# 100_H_M_interface.net
KiCad netlist of a schematic drawn in Altium Designer
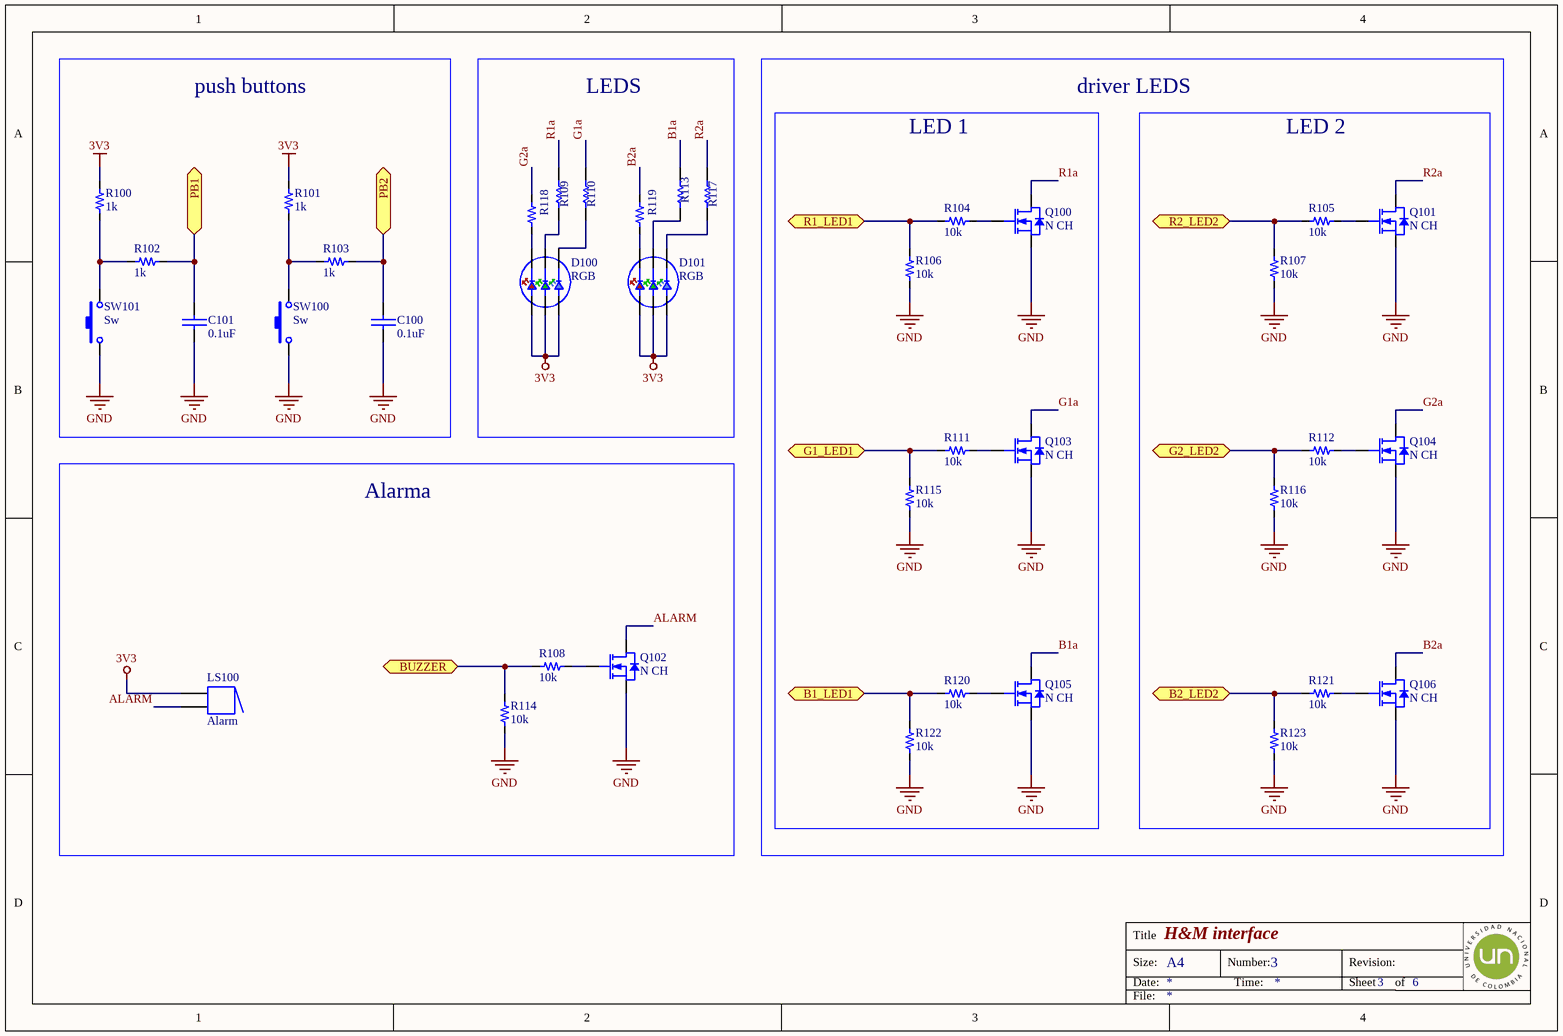
[diagram p0: 100_H&M_interface.SchDoc]

(export (version "E")
  (design (tool "Eeschema 10.0.6"))
  (components
    (comp (ref "C100")
      (value "0.1uF")
      (footprint "0603_cap")
      (description "50V 100nF Y5V -20%~+80% 0603 Multilayer Ceramic Capacitors MLCC - SMD/SMT ROHS")
      (fields
        (field (name "MANUFACTURER") "Walsin Tech Corp")
        (field (name "MANUFACTURER PART NUMBER") "0603F104Z500CT")
      )
      (libsource (lib "shared_lib") (part "Cap_0.1uF_0603_50V"))
    )
    (comp (ref "C101")
      (value "0.1uF")
      (footprint "0603_cap")
      (description "50V 100nF Y5V -20%~+80% 0603 Multilayer Ceramic Capacitors MLCC - SMD/SMT ROHS")
      (fields
        (field (name "MANUFACTURER") "Walsin Tech Corp")
        (field (name "MANUFACTURER PART NUMBER") "0603F104Z500CT")
      )
      (libsource (lib "shared_lib") (part "Cap_0.1uF_0603_50V"))
    )
    (comp (ref "D100")
      (value "RGB")
      (footprint "RGB_NS_3.5X3.7")
      (description "-30℃~+85℃ RGB 110° 3535(mm) Light Emitting Diodes (LED) ROHS")
      (fields
        (field (name "MANUFACTURER") "Foshan NationStar Optoelectronics")
        (field (name "MANUFACTURER PART NUMBER") "RS-3535MWAM")
      )
      (libsource (lib "shared_lib") (part "LED_RGB_3535_SMD"))
    )
    (comp (ref "D101")
      (value "RGB")
      (footprint "RGB_NS_3.5X3.7")
      (description "-30℃~+85℃ RGB 110° 3535(mm) Light Emitting Diodes (LED) ROHS")
      (fields
        (field (name "MANUFACTURER") "Foshan NationStar Optoelectronics")
        (field (name "MANUFACTURER PART NUMBER") "RS-3535MWAM")
      )
      (libsource (lib "shared_lib") (part "LED_RGB_3535_SMD"))
    )
    (comp (ref "LS100")
      (value "Alarm")
      (footprint "Alarm")
      (fields (field (name "MANUFACTURE PART NUMBER") "PS-583Q"))
      (libsource (lib "lib_proj_6") (part "Alarm"))
    )
    (comp (ref "Q100")
      (value "N CH")
      (footprint "SOT_23_3")
      (description "MOSFET N-CH 20V SOT23")
      (fields (field (name "MANUFACTURER") "Doeshare") (field (name "MANUFACTURER PART NUMBER") "DN2302S"))
      (libsource (lib "shared_lib") (part "Q_NFET_20V_3.2A_SOT23"))
    )
    (comp (ref "Q101")
      (value "N CH")
      (footprint "SOT_23_3")
      (description "MOSFET N-CH 20V SOT23")
      (fields (field (name "MANUFACTURER") "Doeshare") (field (name "MANUFACTURER PART NUMBER") "DN2302S"))
      (libsource (lib "shared_lib") (part "Q_NFET_20V_3.2A_SOT23"))
    )
    (comp (ref "Q102")
      (value "N CH")
      (footprint "SOT_23_3")
      (description "MOSFET N-CH 20V SOT23")
      (fields (field (name "MANUFACTURER") "Doeshare") (field (name "MANUFACTURER PART NUMBER") "DN2302S"))
      (libsource (lib "shared_lib") (part "Q_NFET_20V_3.2A_SOT23"))
    )
    (comp (ref "Q103")
      (value "N CH")
      (footprint "SOT_23_3")
      (description "MOSFET N-CH 20V SOT23")
      (fields (field (name "MANUFACTURER") "Doeshare") (field (name "MANUFACTURER PART NUMBER") "DN2302S"))
      (libsource (lib "shared_lib") (part "Q_NFET_20V_3.2A_SOT23"))
    )
    (comp (ref "Q104")
      (value "N CH")
      (footprint "SOT_23_3")
      (description "MOSFET N-CH 20V SOT23")
      (fields (field (name "MANUFACTURER") "Doeshare") (field (name "MANUFACTURER PART NUMBER") "DN2302S"))
      (libsource (lib "shared_lib") (part "Q_NFET_20V_3.2A_SOT23"))
    )
    (comp (ref "Q105")
      (value "N CH")
      (footprint "SOT_23_3")
      (description "MOSFET N-CH 20V SOT23")
      (fields (field (name "MANUFACTURER") "Doeshare") (field (name "MANUFACTURER PART NUMBER") "DN2302S"))
      (libsource (lib "shared_lib") (part "Q_NFET_20V_3.2A_SOT23"))
    )
    (comp (ref "Q106")
      (value "N CH")
      (footprint "SOT_23_3")
      (description "MOSFET N-CH 20V SOT23")
      (fields (field (name "MANUFACTURER") "Doeshare") (field (name "MANUFACTURER PART NUMBER") "DN2302S"))
      (libsource (lib "shared_lib") (part "Q_NFET_20V_3.2A_SOT23"))
    )
    (comp (ref "R100")
      (value "1k")
      (footprint "0603_res")
      (description "RES SMD 1k OHM 5% 1/10W 0603")
      (fields
        (field (name "MANUFACTURER") "FOJAN")
        (field (name "MANUFACTURER PART NUMBER") "FRC0603J102 TS")
      )
      (libsource (lib "shared_lib") (part "Res_1k_0603_1/10W"))
    )
    (comp (ref "R101")
      (value "1k")
      (footprint "0603_res")
      (description "RES SMD 1k OHM 5% 1/10W 0603")
      (fields
        (field (name "MANUFACTURER") "FOJAN")
        (field (name "MANUFACTURER PART NUMBER") "FRC0603J102 TS")
      )
      (libsource (lib "shared_lib") (part "Res_1k_0603_1/10W"))
    )
    (comp (ref "R102")
      (value "1k")
      (footprint "0603_res")
      (description "RES SMD 1k OHM 5% 1/10W 0603")
      (fields
        (field (name "MANUFACTURER") "FOJAN")
        (field (name "MANUFACTURER PART NUMBER") "FRC0603J102 TS")
      )
      (libsource (lib "shared_lib") (part "Res_1k_0603_1/10W"))
    )
    (comp (ref "R103")
      (value "1k")
      (footprint "0603_res")
      (description "RES SMD 1k OHM 5% 1/10W 0603")
      (fields
        (field (name "MANUFACTURER") "FOJAN")
        (field (name "MANUFACTURER PART NUMBER") "FRC0603J102 TS")
      )
      (libsource (lib "shared_lib") (part "Res_1k_0603_1/10W"))
    )
    (comp (ref "R104")
      (value "10k")
      (footprint "0603_res")
      (description "RES SMD 10k OHM 5% 1/10W 0603")
      (fields (field (name "MANUFACTURER") "FOJAN") (field (name "MANUFACTURER PART NUMBER") "FRC0603J103TS"))
      (libsource (lib "shared_lib") (part "Res_10k_0603_1/10W"))
    )
    (comp (ref "R105")
      (value "10k")
      (footprint "0603_res")
      (description "RES SMD 10k OHM 5% 1/10W 0603")
      (fields (field (name "MANUFACTURER") "FOJAN") (field (name "MANUFACTURER PART NUMBER") "FRC0603J103TS"))
      (libsource (lib "shared_lib") (part "Res_10k_0603_1/10W"))
    )
    (comp (ref "R106")
      (value "10k")
      (footprint "0603_res")
      (description "RES SMD 10k OHM 5% 1/10W 0603")
      (fields (field (name "MANUFACTURER") "FOJAN") (field (name "MANUFACTURER PART NUMBER") "FRC0603J103TS"))
      (libsource (lib "shared_lib") (part "Res_10k_0603_1/10W"))
    )
    (comp (ref "R107")
      (value "10k")
      (footprint "0603_res")
      (description "RES SMD 10k OHM 5% 1/10W 0603")
      (fields (field (name "MANUFACTURER") "FOJAN") (field (name "MANUFACTURER PART NUMBER") "FRC0603J103TS"))
      (libsource (lib "shared_lib") (part "Res_10k_0603_1/10W"))
    )
    (comp (ref "R108")
      (value "10k")
      (footprint "0603_res")
      (description "RES SMD 10k OHM 5% 1/10W 0603")
      (fields (field (name "MANUFACTURER") "FOJAN") (field (name "MANUFACTURER PART NUMBER") "FRC0603J103TS"))
      (libsource (lib "shared_lib") (part "Res_10k_0603_1/10W"))
    )
    (comp (ref "R109")
      (value "330R 1/10W")
      (footprint "0603_res")
      (description "100mW Thin Film Resistor ±0.1% 130Ω 0603 Chip Resistor - Surface Mount ROHS")
      (fields
        (field (name "MANUFACTURE PART NUMBER") "PTFR0603B130RP9")
        (field (name "SUPLIER PART NUMBER") "C351683")
      )
      (libsource (lib "lib_proj_6") (part "RES_130R_0603"))
    )
    (comp (ref "R110")
      (value "330R 1/10W")
      (footprint "0603_res")
      (description "100mW Thin Film Resistor ±0.1% 130Ω 0603 Chip Resistor - Surface Mount ROHS")
      (fields
        (field (name "MANUFACTURE PART NUMBER") "PTFR0603B130RP9")
        (field (name "SUPLIER PART NUMBER") "C351683")
      )
      (libsource (lib "lib_proj_6") (part "RES_130R_0603"))
    )
    (comp (ref "R111")
      (value "10k")
      (footprint "0603_res")
      (description "RES SMD 10k OHM 5% 1/10W 0603")
      (fields (field (name "MANUFACTURER") "FOJAN") (field (name "MANUFACTURER PART NUMBER") "FRC0603J103TS"))
      (libsource (lib "shared_lib") (part "Res_10k_0603_1/10W"))
    )
    (comp (ref "R112")
      (value "10k")
      (footprint "0603_res")
      (description "RES SMD 10k OHM 5% 1/10W 0603")
      (fields (field (name "MANUFACTURER") "FOJAN") (field (name "MANUFACTURER PART NUMBER") "FRC0603J103TS"))
      (libsource (lib "shared_lib") (part "Res_10k_0603_1/10W"))
    )
    (comp (ref "R113")
      (value "330R 1/10W")
      (footprint "0603_res")
      (description "100mW Thin Film Resistor ±0.1% 130Ω 0603 Chip Resistor - Surface Mount ROHS")
      (fields
        (field (name "MANUFACTURE PART NUMBER") "PTFR0603B130RP9")
        (field (name "SUPLIER PART NUMBER") "C351683")
      )
      (libsource (lib "lib_proj_6") (part "RES_130R_0603"))
    )
    (comp (ref "R114")
      (value "10k")
      (footprint "0603_res")
      (description "RES SMD 10k OHM 5% 1/10W 0603")
      (fields (field (name "MANUFACTURER") "FOJAN") (field (name "MANUFACTURER PART NUMBER") "FRC0603J103TS"))
      (libsource (lib "shared_lib") (part "Res_10k_0603_1/10W"))
    )
    (comp (ref "R115")
      (value "10k")
      (footprint "0603_res")
      (description "RES SMD 10k OHM 5% 1/10W 0603")
      (fields (field (name "MANUFACTURER") "FOJAN") (field (name "MANUFACTURER PART NUMBER") "FRC0603J103TS"))
      (libsource (lib "shared_lib") (part "Res_10k_0603_1/10W"))
    )
    (comp (ref "R116")
      (value "10k")
      (footprint "0603_res")
      (description "RES SMD 10k OHM 5% 1/10W 0603")
      (fields (field (name "MANUFACTURER") "FOJAN") (field (name "MANUFACTURER PART NUMBER") "FRC0603J103TS"))
      (libsource (lib "shared_lib") (part "Res_10k_0603_1/10W"))
    )
    (comp (ref "R117")
      (value "330R 1/10W")
      (footprint "0603_res")
      (description "100mW Thin Film Resistor ±0.1% 130Ω 0603 Chip Resistor - Surface Mount ROHS")
      (fields
        (field (name "MANUFACTURE PART NUMBER") "PTFR0603B130RP9")
        (field (name "SUPLIER PART NUMBER") "C351683")
      )
      (libsource (lib "lib_proj_6") (part "RES_130R_0603"))
    )
    (comp (ref "R118")
      (value "330R 1/10W")
      (footprint "0603_res")
      (description "RES SMD 100R OHM 5% 1/10W 0603")
      (fields
        (field (name "MANUFACTURER") "FOJAN")
        (field (name "MANUFACTURER PART NUMBER") "FRC0603J101 TS")
      )
      (libsource (lib "shared_lib") (part "Res_100R_0603_1/10W"))
    )
    (comp (ref "R119")
      (value "330R 1/10W")
      (footprint "0603_res")
      (description "RES SMD 100R OHM 5% 1/10W 0603")
      (fields
        (field (name "MANUFACTURER") "FOJAN")
        (field (name "MANUFACTURER PART NUMBER") "FRC0603J101 TS")
      )
      (libsource (lib "shared_lib") (part "Res_100R_0603_1/10W"))
    )
    (comp (ref "R120")
      (value "10k")
      (footprint "0603_res")
      (description "RES SMD 10k OHM 5% 1/10W 0603")
      (fields (field (name "MANUFACTURER") "FOJAN") (field (name "MANUFACTURER PART NUMBER") "FRC0603J103TS"))
      (libsource (lib "shared_lib") (part "Res_10k_0603_1/10W"))
    )
    (comp (ref "R121")
      (value "10k")
      (footprint "0603_res")
      (description "RES SMD 10k OHM 5% 1/10W 0603")
      (fields (field (name "MANUFACTURER") "FOJAN") (field (name "MANUFACTURER PART NUMBER") "FRC0603J103TS"))
      (libsource (lib "shared_lib") (part "Res_10k_0603_1/10W"))
    )
    (comp (ref "R122")
      (value "10k")
      (footprint "0603_res")
      (description "RES SMD 10k OHM 5% 1/10W 0603")
      (fields (field (name "MANUFACTURER") "FOJAN") (field (name "MANUFACTURER PART NUMBER") "FRC0603J103TS"))
      (libsource (lib "shared_lib") (part "Res_10k_0603_1/10W"))
    )
    (comp (ref "R123")
      (value "10k")
      (footprint "0603_res")
      (description "RES SMD 10k OHM 5% 1/10W 0603")
      (fields (field (name "MANUFACTURER") "FOJAN") (field (name "MANUFACTURER PART NUMBER") "FRC0603J103TS"))
      (libsource (lib "shared_lib") (part "Res_10k_0603_1/10W"))
    )
    (comp (ref "SW100")
      (value "Sw")
      (footprint "Sw_PUSH_4.5x4.5x5mm")
      (description "SWITCH TACTILE SPST-NO 0.05A 12V")
      (fields
        (field (name "MANUFACTURER") "BZCN")
        (field (name "MANUFACTURER PART NUMBER") "TSC015A05026A")
        (field (name "LAST MODIFIED BY") "N-A.Potosi")
      )
      (libsource (lib "shared_lib") (part "Sw_PUSH_4.5x4.5x5.0xmm"))
    )
    (comp (ref "SW101")
      (value "Sw")
      (footprint "Sw_PUSH_4.5x4.5x5mm")
      (description "SWITCH TACTILE SPST-NO 0.05A 12V")
      (fields
        (field (name "MANUFACTURER") "BZCN")
        (field (name "MANUFACTURER PART NUMBER") "TSC015A05026A")
        (field (name "LAST MODIFIED BY") "N-A.Potosi")
      )
      (libsource (lib "shared_lib") (part "Sw_PUSH_4.5x4.5x5.0xmm"))
    )
  )
  (nets
    (net (code "1") (name "/ALARM") (class "Default")
      (node (ref "LS100") (pin "1") (pinfunction "2A_1") (pintype "passive"))
      (node (ref "Q102") (pin "3") (pinfunction "D_3") (pintype "passive"))
    )
    (net (code "2") (name "/B1_LED1") (class "Default")
      (node (ref "R120") (pin "1") (pinfunction "1_1") (pintype "passive"))
      (node (ref "R122") (pin "2") (pinfunction "2_2") (pintype "passive"))
    )
    (net (code "3") (name "/B1a") (class "Default")
      (node (ref "Q105") (pin "3") (pinfunction "D_3") (pintype "passive"))
      (node (ref "R113") (pin "2") (pinfunction "2_2") (pintype "passive"))
    )
    (net (code "4") (name "/B2_LED2") (class "Default")
      (node (ref "R121") (pin "1") (pinfunction "1_1") (pintype "passive"))
      (node (ref "R123") (pin "2") (pinfunction "2_2") (pintype "passive"))
    )
    (net (code "5") (name "/B2a") (class "Default")
      (node (ref "Q106") (pin "3") (pinfunction "D_3") (pintype "passive"))
      (node (ref "R119") (pin "2") (pinfunction "2_2") (pintype "passive"))
    )
    (net (code "6") (name "/BUZZER") (class "Default")
      (node (ref "R108") (pin "1") (pinfunction "1_1") (pintype "passive"))
      (node (ref "R114") (pin "2") (pinfunction "2_2") (pintype "passive"))
    )
    (net (code "7") (name "/G1_LED1") (class "Default")
      (node (ref "R111") (pin "1") (pinfunction "1_1") (pintype "passive"))
      (node (ref "R115") (pin "2") (pinfunction "2_2") (pintype "passive"))
    )
    (net (code "8") (name "/G1a") (class "Default")
      (node (ref "Q103") (pin "3") (pinfunction "D_3") (pintype "passive"))
      (node (ref "R110") (pin "2") (pinfunction "2_2") (pintype "passive"))
    )
    (net (code "9") (name "/G2_LED2") (class "Default")
      (node (ref "R112") (pin "1") (pinfunction "1_1") (pintype "passive"))
      (node (ref "R116") (pin "2") (pinfunction "2_2") (pintype "passive"))
    )
    (net (code "10") (name "/G2a") (class "Default")
      (node (ref "Q104") (pin "3") (pinfunction "D_3") (pintype "passive"))
      (node (ref "R118") (pin "2") (pinfunction "2_2") (pintype "passive"))
    )
    (net (code "11") (name "/PB1") (class "Default")
      (node (ref "C101") (pin "2") (pinfunction "2_2") (pintype "passive"))
      (node (ref "R102") (pin "1") (pinfunction "1_1") (pintype "passive"))
    )
    (net (code "12") (name "/PB2") (class "Default")
      (node (ref "C100") (pin "2") (pinfunction "2_2") (pintype "passive"))
      (node (ref "R103") (pin "1") (pinfunction "1_1") (pintype "passive"))
    )
    (net (code "13") (name "/R1_LED1") (class "Default")
      (node (ref "R104") (pin "1") (pinfunction "1_1") (pintype "passive"))
      (node (ref "R106") (pin "2") (pinfunction "2_2") (pintype "passive"))
    )
    (net (code "14") (name "/R1a") (class "Default")
      (node (ref "Q100") (pin "3") (pinfunction "D_3") (pintype "passive"))
      (node (ref "R109") (pin "2") (pinfunction "2_2") (pintype "passive"))
    )
    (net (code "15") (name "/R2_LED2") (class "Default")
      (node (ref "R105") (pin "1") (pinfunction "1_1") (pintype "passive"))
      (node (ref "R107") (pin "2") (pinfunction "2_2") (pintype "passive"))
    )
    (net (code "16") (name "/R2a") (class "Default")
      (node (ref "Q101") (pin "3") (pinfunction "D_3") (pintype "passive"))
      (node (ref "R117") (pin "2") (pinfunction "2_2") (pintype "passive"))
    )
    (net (code "17") (name "3V3") (class "Default")
      (node (ref "D100") (pin "4") (pinfunction "4_4") (pintype "passive"))
      (node (ref "D100") (pin "5") (pinfunction "5_5") (pintype "passive"))
      (node (ref "D100") (pin "6") (pinfunction "6_6") (pintype "passive"))
      (node (ref "D101") (pin "4") (pinfunction "4_4") (pintype "passive"))
      (node (ref "D101") (pin "5") (pinfunction "5_5") (pintype "passive"))
      (node (ref "D101") (pin "6") (pinfunction "6_6") (pintype "passive"))
      (node (ref "LS100") (pin "0") (pinfunction "1_0") (pintype "passive"))
      (node (ref "R100") (pin "2") (pinfunction "2_2") (pintype "passive"))
      (node (ref "R101") (pin "2") (pinfunction "2_2") (pintype "passive"))
    )
    (net (code "18") (name "GND") (class "Default")
      (node (ref "C100") (pin "1") (pinfunction "1_1") (pintype "passive"))
      (node (ref "C101") (pin "1") (pinfunction "1_1") (pintype "passive"))
      (node (ref "Q100") (pin "2") (pinfunction "S_2") (pintype "passive"))
      (node (ref "Q101") (pin "2") (pinfunction "S_2") (pintype "passive"))
      (node (ref "Q102") (pin "2") (pinfunction "S_2") (pintype "passive"))
      (node (ref "Q103") (pin "2") (pinfunction "S_2") (pintype "passive"))
      (node (ref "Q104") (pin "2") (pinfunction "S_2") (pintype "passive"))
      (node (ref "Q105") (pin "2") (pinfunction "S_2") (pintype "passive"))
      (node (ref "Q106") (pin "2") (pinfunction "S_2") (pintype "passive"))
      (node (ref "R106") (pin "1") (pinfunction "1_1") (pintype "passive"))
      (node (ref "R107") (pin "1") (pinfunction "1_1") (pintype "passive"))
      (node (ref "R114") (pin "1") (pinfunction "1_1") (pintype "passive"))
      (node (ref "R115") (pin "1") (pinfunction "1_1") (pintype "passive"))
      (node (ref "R116") (pin "1") (pinfunction "1_1") (pintype "passive"))
      (node (ref "R122") (pin "1") (pinfunction "1_1") (pintype "passive"))
      (node (ref "R123") (pin "1") (pinfunction "1_1") (pintype "passive"))
      (node (ref "SW100") (pin "1") (pinfunction "1_1") (pintype "passive"))
      (node (ref "SW101") (pin "1") (pinfunction "1_1") (pintype "passive"))
    )
    (net (code "19") (name "Net-(D100-Pad1)") (class "Default")
      (node (ref "D100") (pin "1") (pinfunction "1_1") (pintype "passive"))
      (node (ref "R110") (pin "1") (pinfunction "1_1") (pintype "passive"))
    )
    (net (code "20") (name "Net-(D100-Pad2)") (class "Default")
      (node (ref "D100") (pin "2") (pinfunction "2_2") (pintype "passive"))
      (node (ref "R109") (pin "1") (pinfunction "1_1") (pintype "passive"))
    )
    (net (code "21") (name "Net-(D100-Pad3)") (class "Default")
      (node (ref "D100") (pin "3") (pinfunction "3_3") (pintype "passive"))
      (node (ref "R118") (pin "1") (pinfunction "1_1") (pintype "passive"))
    )
    (net (code "22") (name "Net-(D101-Pad1)") (class "Default")
      (node (ref "D101") (pin "1") (pinfunction "1_1") (pintype "passive"))
      (node (ref "R117") (pin "1") (pinfunction "1_1") (pintype "passive"))
    )
    (net (code "23") (name "Net-(D101-Pad2)") (class "Default")
      (node (ref "D101") (pin "2") (pinfunction "2_2") (pintype "passive"))
      (node (ref "R113") (pin "1") (pinfunction "1_1") (pintype "passive"))
    )
    (net (code "24") (name "Net-(D101-Pad3)") (class "Default")
      (node (ref "D101") (pin "3") (pinfunction "3_3") (pintype "passive"))
      (node (ref "R119") (pin "1") (pinfunction "1_1") (pintype "passive"))
    )
    (net (code "25") (name "Net-(Q100-G)") (class "Default")
      (node (ref "Q100") (pin "1") (pinfunction "G_1") (pintype "passive"))
      (node (ref "R104") (pin "2") (pinfunction "2_2") (pintype "passive"))
    )
    (net (code "26") (name "Net-(Q101-G)") (class "Default")
      (node (ref "Q101") (pin "1") (pinfunction "G_1") (pintype "passive"))
      (node (ref "R105") (pin "2") (pinfunction "2_2") (pintype "passive"))
    )
    (net (code "27") (name "Net-(Q102-G)") (class "Default")
      (node (ref "Q102") (pin "1") (pinfunction "G_1") (pintype "passive"))
      (node (ref "R108") (pin "2") (pinfunction "2_2") (pintype "passive"))
    )
    (net (code "28") (name "Net-(Q103-G)") (class "Default")
      (node (ref "Q103") (pin "1") (pinfunction "G_1") (pintype "passive"))
      (node (ref "R111") (pin "2") (pinfunction "2_2") (pintype "passive"))
    )
    (net (code "29") (name "Net-(Q104-G)") (class "Default")
      (node (ref "Q104") (pin "1") (pinfunction "G_1") (pintype "passive"))
      (node (ref "R112") (pin "2") (pinfunction "2_2") (pintype "passive"))
    )
    (net (code "30") (name "Net-(Q105-G)") (class "Default")
      (node (ref "Q105") (pin "1") (pinfunction "G_1") (pintype "passive"))
      (node (ref "R120") (pin "2") (pinfunction "2_2") (pintype "passive"))
    )
    (net (code "31") (name "Net-(Q106-G)") (class "Default")
      (node (ref "Q106") (pin "1") (pinfunction "G_1") (pintype "passive"))
      (node (ref "R121") (pin "2") (pinfunction "2_2") (pintype "passive"))
    )
    (net (code "32") (name "Net-(R100-Pad1)") (class "Default")
      (node (ref "R100") (pin "1") (pinfunction "1_1") (pintype "passive"))
      (node (ref "R102") (pin "2") (pinfunction "2_2") (pintype "passive"))
      (node (ref "SW101") (pin "2") (pinfunction "2_2") (pintype "passive"))
    )
    (net (code "33") (name "Net-(R101-Pad1)") (class "Default")
      (node (ref "R101") (pin "1") (pinfunction "1_1") (pintype "passive"))
      (node (ref "R103") (pin "2") (pinfunction "2_2") (pintype "passive"))
      (node (ref "SW100") (pin "2") (pinfunction "2_2") (pintype "passive"))
    )
  )
)
